# monostable.net
KiCad netlist of a schematic drawn in EAGLE
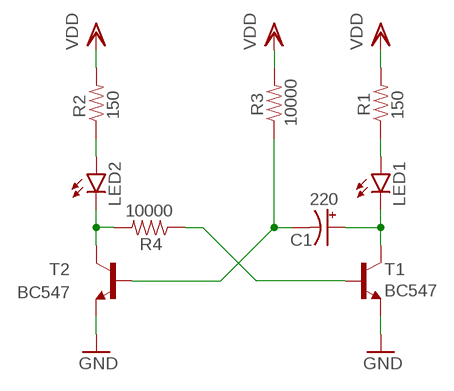
[diagram p0: schematic, sheet 1]

(export (version "E")
  (design (tool "Eeschema 10.0.6"))
  (components
    (comp (ref "C1")
      (value "220")
      (footprint "eagle-import:CPOL-RADIAL-1000UF-25V")
      (libsource (lib "eagle-import") (part "CAP_POLPTH4"))
    )
    (comp (ref "LED1")
      (value "LED5MM")
      (footprint "eagle-import:LED5MM")
      (libsource (lib "eagle-import") (part "LED5MM"))
    )
    (comp (ref "LED2")
      (value "LED5MM")
      (footprint "eagle-import:LED5MM")
      (libsource (lib "eagle-import") (part "LED5MM"))
    )
    (comp (ref "R1")
      (value "150")
      (footprint "eagle-import:AXIAL-0.5")
      (libsource (lib "eagle-import") (part "RESISTORPTH-1/2W"))
    )
    (comp (ref "R2")
      (value "150")
      (footprint "eagle-import:AXIAL-0.5")
      (libsource (lib "eagle-import") (part "RESISTORPTH-1/2W"))
    )
    (comp (ref "R3")
      (value "10000")
      (footprint "eagle-import:AXIAL-0.5")
      (libsource (lib "eagle-import") (part "RESISTORPTH-1/2W"))
    )
    (comp (ref "R4")
      (value "10000")
      (footprint "eagle-import:AXIAL-0.5")
      (libsource (lib "eagle-import") (part "RESISTORPTH-1/2W"))
    )
    (comp (ref "T1")
      (value "BC547")
      (footprint "eagle-import:TO92")
      (libsource (lib "eagle-import") (part "BC547"))
    )
    (comp (ref "T2")
      (value "BC547")
      (footprint "eagle-import:TO92")
      (libsource (lib "eagle-import") (part "BC547"))
    )
  )
  (nets
    (net (code "1") (name "GND") (class "Default")
      (node (ref "T1") (pin "1") (pinfunction "E_1") (pintype "passive"))
      (node (ref "T2") (pin "1") (pinfunction "E_1") (pintype "passive"))
    )
    (net (code "2") (name "Net-(C1-+)") (class "Default")
      (node (ref "C1") (pin "1") (pinfunction "+_1") (pintype "passive"))
      (node (ref "LED1") (pin "K") (pinfunction "C_K") (pintype "passive"))
      (node (ref "T1") (pin "3") (pinfunction "C_3") (pintype "passive"))
    )
    (net (code "3") (name "Net-(C1--)") (class "Default")
      (node (ref "C1") (pin "2") (pinfunction "-_2") (pintype "passive"))
      (node (ref "R3") (pin "P$1") (pinfunction "1_P$1") (pintype "passive"))
      (node (ref "T2") (pin "2") (pinfunction "B_2") (pintype "passive"))
    )
    (net (code "4") (name "Net-(LED2-C)") (class "Default")
      (node (ref "LED2") (pin "K") (pinfunction "C_K") (pintype "passive"))
      (node (ref "R4") (pin "P$2") (pinfunction "2_P$2") (pintype "passive"))
      (node (ref "T2") (pin "3") (pinfunction "C_3") (pintype "passive"))
    )
    (net (code "5") (name "Net-(R1-1)") (class "Default")
      (node (ref "LED1") (pin "A") (pinfunction "A_A") (pintype "passive"))
      (node (ref "R1") (pin "P$1") (pinfunction "1_P$1") (pintype "passive"))
    )
    (net (code "6") (name "Net-(R2-1)") (class "Default")
      (node (ref "LED2") (pin "A") (pinfunction "A_A") (pintype "passive"))
      (node (ref "R2") (pin "P$1") (pinfunction "1_P$1") (pintype "passive"))
    )
    (net (code "7") (name "Net-(R4-1)") (class "Default")
      (node (ref "R4") (pin "P$1") (pinfunction "1_P$1") (pintype "passive"))
      (node (ref "T1") (pin "2") (pinfunction "B_2") (pintype "passive"))
    )
    (net (code "8") (name "VDD") (class "Default")
      (node (ref "R1") (pin "P$2") (pinfunction "2_P$2") (pintype "passive"))
      (node (ref "R2") (pin "P$2") (pinfunction "2_P$2") (pintype "passive"))
      (node (ref "R3") (pin "P$2") (pinfunction "2_P$2") (pintype "passive"))
    )
  )
)
